# PanelDriver.net
KiCad netlist of a schematic drawn in Altium Designer
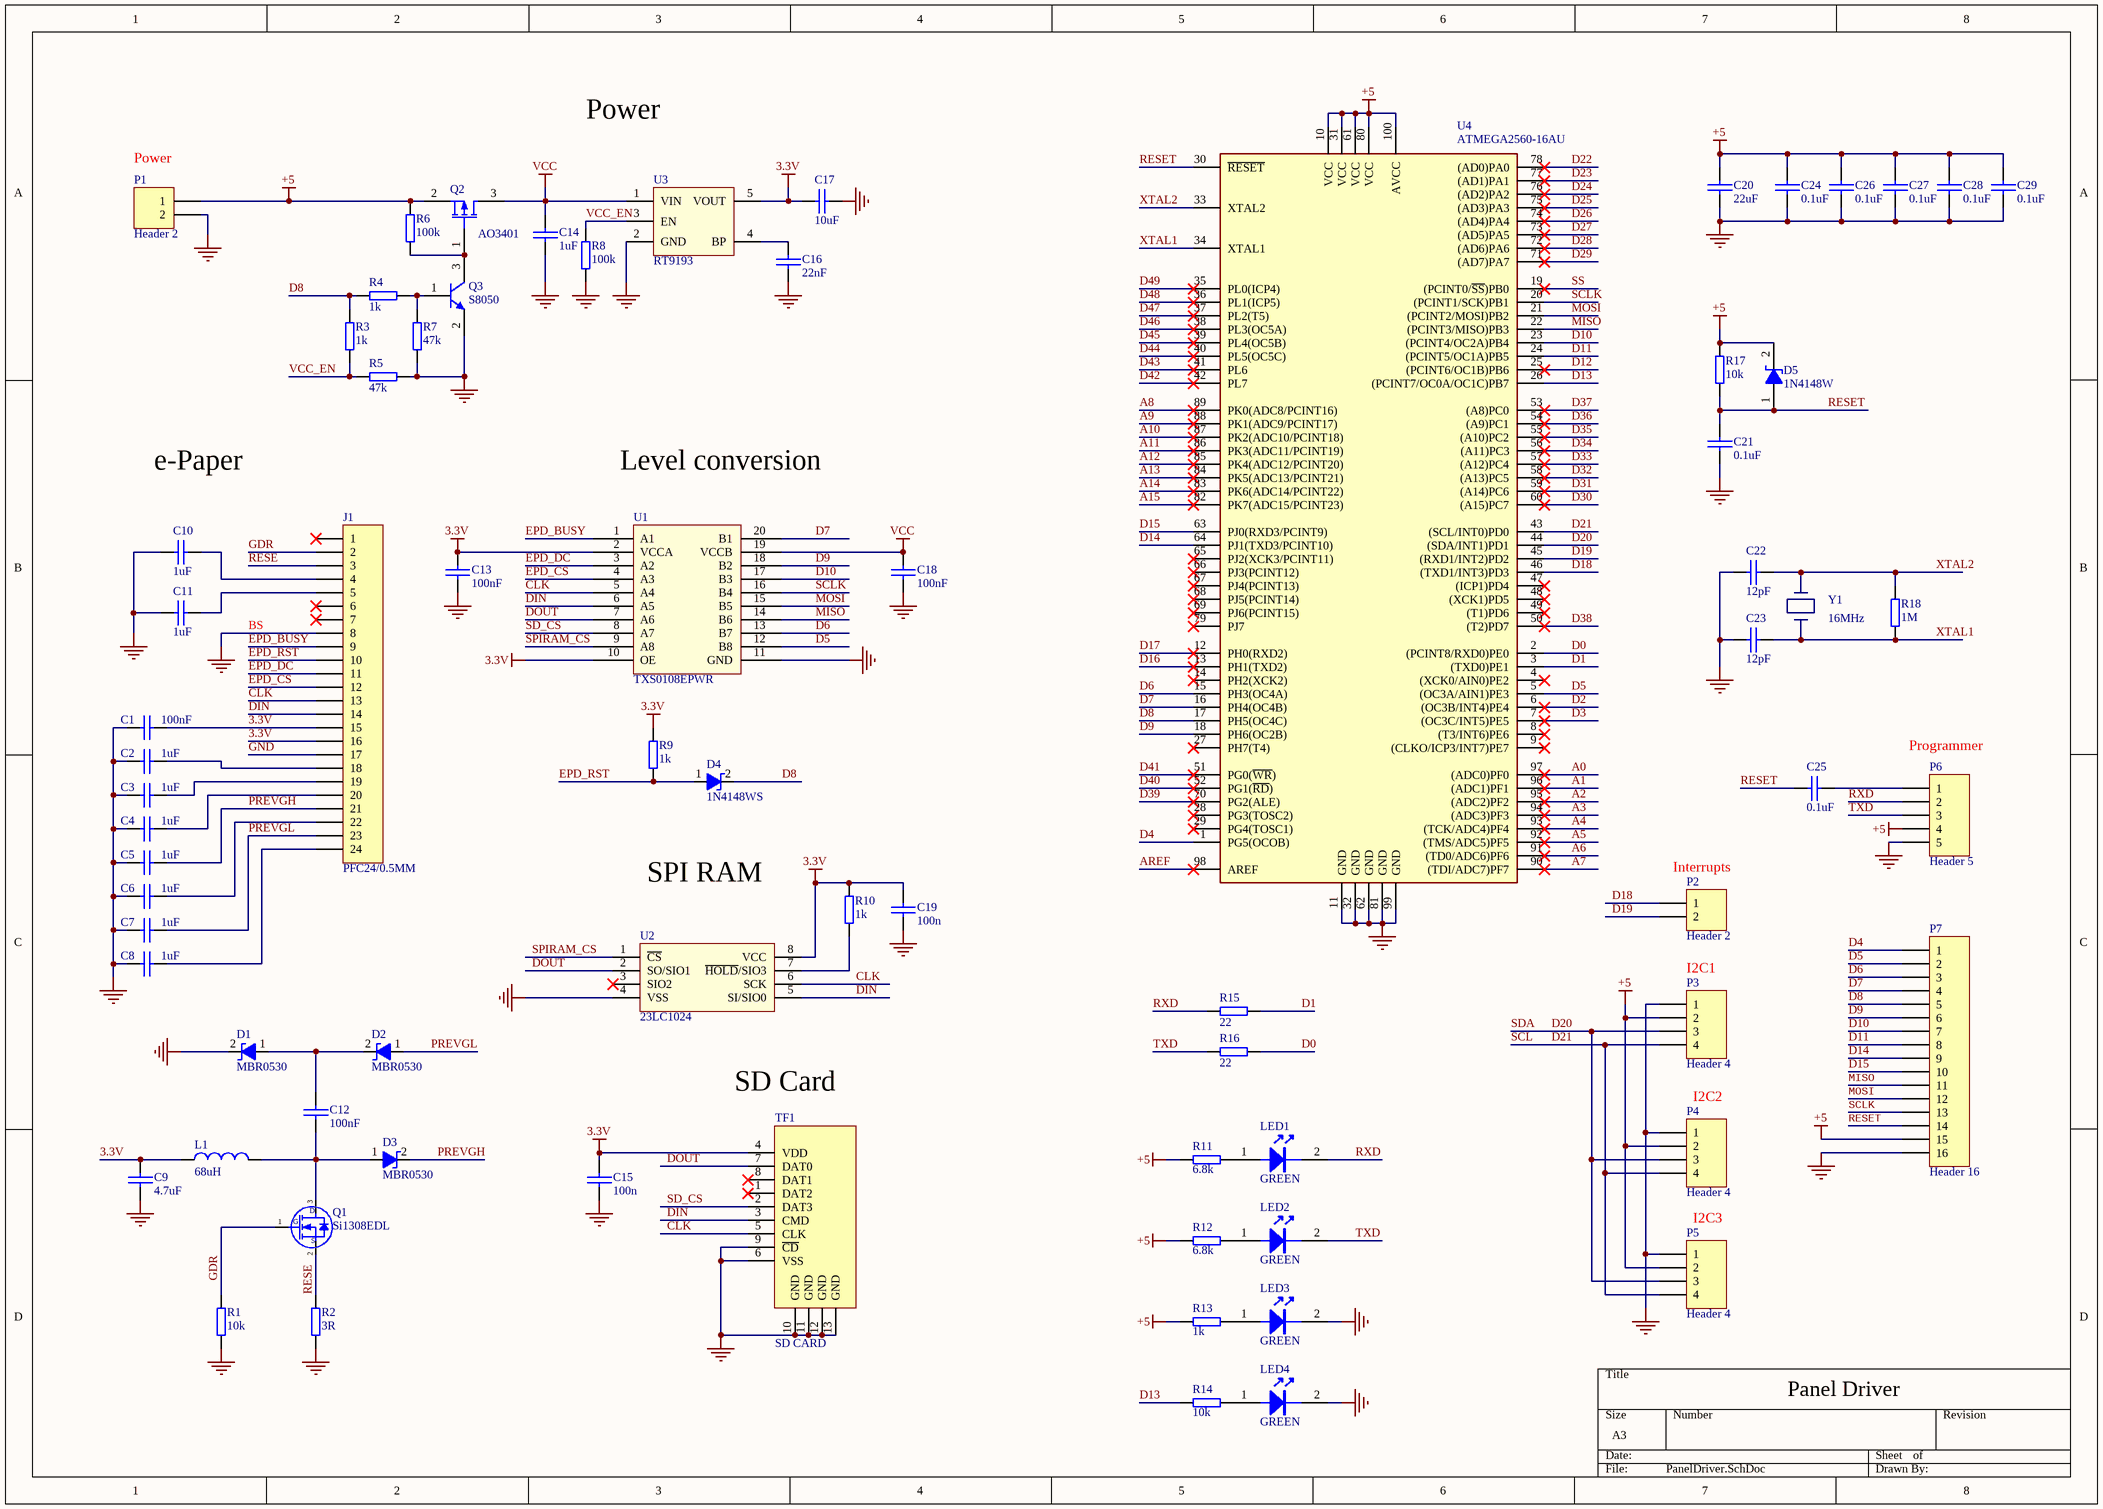
[diagram p0: PanelDriver.SchDoc]

(export (version "E")
  (design (tool "Eeschema 10.0.6"))
  (components
    (comp (ref "C1")
      (value "100nF")
      (footprint "C0603")
      (description "Capacitor")
      (fields (field (name "MANUFACTURER") "Any"))
      (libsource (lib "*") (part "C"))
    )
    (comp (ref "C2")
      (value "1uF")
      (footprint "C0603")
      (description "Capacitor")
      (fields (field (name "MANUFACTURER") "Any"))
      (libsource (lib "*") (part "C"))
    )
    (comp (ref "C3")
      (value "1uF")
      (footprint "C0603")
      (description "Capacitor")
      (fields (field (name "MANUFACTURER") "Any"))
      (libsource (lib "*") (part "C"))
    )
    (comp (ref "C4")
      (value "1uF")
      (footprint "C0603")
      (description "Capacitor")
      (fields (field (name "MANUFACTURER") "Any"))
      (libsource (lib "*") (part "C"))
    )
    (comp (ref "C5")
      (value "1uF")
      (footprint "C0603")
      (description "Capacitor")
      (fields (field (name "MANUFACTURER") "Any"))
      (libsource (lib "*") (part "C"))
    )
    (comp (ref "C6")
      (value "1uF")
      (footprint "C0603")
      (description "Capacitor")
      (fields (field (name "MANUFACTURER") "Any"))
      (libsource (lib "*") (part "C"))
    )
    (comp (ref "C7")
      (value "1uF")
      (footprint "C0603")
      (description "Capacitor")
      (fields (field (name "MANUFACTURER") "Any"))
      (libsource (lib "*") (part "C"))
    )
    (comp (ref "C8")
      (value "1uF")
      (footprint "C0603")
      (description "Capacitor")
      (fields (field (name "MANUFACTURER") "Any"))
      (libsource (lib "*") (part "C"))
    )
    (comp (ref "C9")
      (value "4.7uF")
      (footprint "C0603")
      (description "Capacitor")
      (fields (field (name "MANUFACTURER") "Any"))
      (libsource (lib "*") (part "C"))
    )
    (comp (ref "C10")
      (value "1uF")
      (footprint "C0603")
      (description "Capacitor")
      (fields (field (name "MANUFACTURER") "Any"))
      (libsource (lib "*") (part "C"))
    )
    (comp (ref "C11")
      (value "1uF")
      (footprint "C0603")
      (description "Capacitor")
      (fields (field (name "MANUFACTURER") "Any"))
      (libsource (lib "*") (part "C"))
    )
    (comp (ref "C12")
      (value "100nF")
      (footprint "C0603")
      (description "Capacitor")
      (fields (field (name "MANUFACTURER") "Any"))
      (libsource (lib "*") (part "C"))
    )
    (comp (ref "C13")
      (value "100nF")
      (footprint "C0603")
      (description "Capacitor")
      (fields (field (name "MANUFACTURER") "Any"))
      (libsource (lib "*") (part "C"))
    )
    (comp (ref "C14")
      (value "1uF")
      (footprint "C0603")
      (description "Capacitor")
      (fields (field (name "MANUFACTURER") "Any"))
      (libsource (lib "*") (part "C"))
    )
    (comp (ref "C15")
      (value "100n")
      (footprint "C0603")
      (description "Capacitor")
      (fields (field (name "MANUFACTURER") "Any"))
      (libsource (lib "*") (part "C"))
    )
    (comp (ref "C16")
      (value "22nF")
      (footprint "C0603")
      (description "Capacitor")
      (fields (field (name "VOLTAGE") "6.3V") (field (name "MANUFACTURER") "Any"))
      (libsource (lib "OE Modbus EMU") (part "C_100uF_6.3V_1206"))
    )
    (comp (ref "C17")
      (value "10uF")
      (footprint "C0603")
      (description "Capacitor")
      (fields (field (name "VOLTAGE") "6.3V") (field (name "MANUFACTURER") "Any"))
      (libsource (lib "OE Modbus EMU") (part "C_100uF_6.3V_1206"))
    )
    (comp (ref "C18")
      (value "100nF")
      (footprint "C0603")
      (description "Capacitor")
      (fields (field (name "MANUFACTURER") "Any"))
      (libsource (lib "*") (part "C"))
    )
    (comp (ref "C19")
      (value "100n")
      (footprint "C0603")
      (description "Capacitor")
      (fields (field (name "MANUFACTURER") "Any"))
      (libsource (lib "*") (part "C"))
    )
    (comp (ref "C20")
      (value "22uF")
      (footprint "C1206")
      (description "16V 22uF X7R ±10% 1206  Multilayer Ceramic Capacitors MLCC - SMD/SMT ROHS")
      (fields (field (name "MANUFACTURER") "Any"))
      (libsource (lib "*") (part "C"))
    )
    (comp (ref "C21")
      (value "0.1uF")
      (footprint "C0603")
      (description "25V 100nF X7R ±10% 0603  Multilayer Ceramic Capacitors MLCC - SMD/SMT ROHS")
      (fields (field (name "MANUFACTURER") "Any"))
      (libsource (lib "*") (part "C"))
    )
    (comp (ref "C22")
      (value "12pF")
      (footprint "C0603")
      (description "50V 22pF X7R ±10% 0603  Multilayer Ceramic Capacitors MLCC - SMD/SMT ROHS")
      (fields (field (name "VOLTAGE") "6.3V") (field (name "MANUFACTURER") "Any"))
      (libsource (lib "OE Modbus EMU") (part "C_100uF_6.3V_1206"))
    )
    (comp (ref "C23")
      (value "12pF")
      (footprint "C0603")
      (description "50V 22pF X7R ±10% 0603  Multilayer Ceramic Capacitors MLCC - SMD/SMT ROHS")
      (fields (field (name "VOLTAGE") "6.3V") (field (name "MANUFACTURER") "Any"))
      (libsource (lib "OE Modbus EMU") (part "C_100uF_6.3V_1206"))
    )
    (comp (ref "C24")
      (value "0.1uF")
      (footprint "C0603")
      (description "25V 100nF X7R ±10% 0603  Multilayer Ceramic Capacitors MLCC - SMD/SMT ROHS")
      (fields (field (name "MANUFACTURER") "Any"))
      (libsource (lib "*") (part "C"))
    )
    (comp (ref "C25")
      (value "0.1uF")
      (footprint "C0603")
      (description "25V 100nF X7R ±10% 0603  Multilayer Ceramic Capacitors MLCC - SMD/SMT ROHS")
      (fields (field (name "MANUFACTURER") "Any"))
      (libsource (lib "*") (part "C"))
    )
    (comp (ref "C26")
      (value "0.1uF")
      (footprint "C0603")
      (description "25V 100nF X7R ±10% 0603  Multilayer Ceramic Capacitors MLCC - SMD/SMT ROHS")
      (fields (field (name "MANUFACTURER") "Any"))
      (libsource (lib "*") (part "C"))
    )
    (comp (ref "C27")
      (value "0.1uF")
      (footprint "C0603")
      (description "25V 100nF X7R ±10% 0603  Multilayer Ceramic Capacitors MLCC - SMD/SMT ROHS")
      (fields (field (name "MANUFACTURER") "Any"))
      (libsource (lib "*") (part "C"))
    )
    (comp (ref "C28")
      (value "0.1uF")
      (footprint "C0603")
      (description "25V 100nF X7R ±10% 0603  Multilayer Ceramic Capacitors MLCC - SMD/SMT ROHS")
      (fields (field (name "MANUFACTURER") "Any") (field (name "JLCPCB PART NUMBER") "C307361"))
      (libsource (lib "") (part "C_1"))
    )
    (comp (ref "C29")
      (value "0.1uF")
      (footprint "C0603")
      (description "25V 100nF X7R ±10% 0603  Multilayer Ceramic Capacitors MLCC - SMD/SMT ROHS")
      (fields (field (name "MANUFACTURER") "Any"))
      (libsource (lib "*") (part "C"))
    )
    (comp (ref "D1")
      (value "MBR0530")
      (footprint "SOD123")
      (fields (field (name "MANUFACTURER") "Any"))
      (libsource (lib "OE Modbus EMU") (part "SS14F"))
    )
    (comp (ref "D2")
      (value "MBR0530")
      (footprint "SOD123")
      (fields (field (name "MANUFACTURER") "Any"))
      (libsource (lib "OE Modbus EMU") (part "SS14F"))
    )
    (comp (ref "D3")
      (value "MBR0530")
      (footprint "SOD123")
      (fields (field (name "MANUFACTURER") "Any"))
      (libsource (lib "OE Modbus EMU") (part "SS14F"))
    )
    (comp (ref "D4")
      (value "1N4148WS")
      (footprint "SOD-323")
      (fields (field (name "MANUFACTURER") "Any"))
      (libsource (lib "OE Modbus EMU") (part "SS14F"))
    )
    (comp (ref "D5")
      (value "1N4148W")
      (footprint "SOD123")
      (description "1N4148W-E3-08, Rectifier Diode Small Signal Switching Si 100V 0.15A 4ns 2-Pin SOD-123 T/R")
      (fields (field (name "MANUFACTURER") "Any"))
      (libsource (lib "A2560") (part "SS14F"))
    )
    (comp (ref "J1")
      (value "PFC24/0.5MM")
      (footprint "PFC24/0.5MM")
      (description "24 Position FFC, FPC Connector Contacts, Bottom 0.020\" (0.50mm) Surface Mount, Right Angle")
      (fields
        (field (name "MANUFACTURER") "MOLEX")
        (field (name "MANUFACTURER PART NUMBER") "0524372471")
        (field (name "PUBLISHER") "Altium Limited")
      )
      (libsource (lib "PanelDriver") (part "PFC24/0.5MMHeader 24"))
    )
    (comp (ref "L1")
      (value "68uH")
      (footprint "CD43")
      (description "SMD, 4x4mm  Inductor")
      (fields (field (name "MANUFACTURER") "Any"))
      (libsource (lib "OE Modbus EMU") (part "IND"))
    )
    (comp (ref "LED1")
      (value "GREEN")
      (footprint "LED-0603-GREEN")
      (description "0603  Light Emitting Diodes (LED) ROHS")
      (fields (field (name "MANUFACTURER") "Any") (field (name "JLCPCB PART NUMBER") "C965812"))
      (libsource (lib "A2560") (part "LED"))
    )
    (comp (ref "LED2")
      (value "GREEN")
      (footprint "LED-0603-GREEN")
      (description "0603  Light Emitting Diodes (LED) ROHS")
      (fields (field (name "MANUFACTURER") "Any") (field (name "JLCPCB PART NUMBER") "C965812"))
      (libsource (lib "A2560") (part "LED"))
    )
    (comp (ref "LED3")
      (value "GREEN")
      (footprint "LED-0603-GREEN")
      (description "0603  Light Emitting Diodes (LED) ROHS")
      (fields (field (name "MANUFACTURER") "Any") (field (name "JLCPCB PART NUMBER") "C965812"))
      (libsource (lib "A2560") (part "LED"))
    )
    (comp (ref "LED4")
      (value "GREEN")
      (footprint "LED-0603-GREEN")
      (description "0603  Light Emitting Diodes (LED) ROHS")
      (fields (field (name "MANUFACTURER") "Any") (field (name "JLCPCB PART NUMBER") "C965812"))
      (libsource (lib "A2560") (part "LED"))
    )
    (comp (ref "P1")
      (value "Header 2")
      (footprint "HDR1X2")
      (description "Header, 2-Pin")
      (fields (field (name "PUBLISHER") "Altium Limited"))
      (libsource (lib "") (part "Header 2_1"))
    )
    (comp (ref "P2")
      (value "Header 2")
      (footprint "HDR1X2")
      (description "Header, 2-Pin")
      (fields (field (name "PUBLISHER") "Altium Limited"))
      (libsource (lib "Miscellaneous Connectors") (part "Header 2"))
    )
    (comp (ref "P3")
      (value "Header 4")
      (footprint "HDR1X4")
      (description "Header, 4-Pin")
      (fields (field (name "PUBLISHER") "Altium Limited"))
      (libsource (lib "Miscellaneous Connectors") (part "Header 4"))
    )
    (comp (ref "P4")
      (value "Header 4")
      (footprint "HDR1X4")
      (description "Header, 4-Pin")
      (fields (field (name "PUBLISHER") "Altium Limited"))
      (libsource (lib "Miscellaneous Connectors") (part "Header 4"))
    )
    (comp (ref "P5")
      (value "Header 4")
      (footprint "HDR1X4")
      (description "Header, 4-Pin")
      (fields (field (name "PUBLISHER") "Altium Limited"))
      (libsource (lib "Miscellaneous Connectors") (part "Header 4"))
    )
    (comp (ref "P6")
      (value "Header 5")
      (footprint "HDR1X5")
      (description "Header, 5-Pin")
      (fields (field (name "MANUFACTURER") "Any") (field (name "PUBLISHER") "Altium Limited"))
      (libsource (lib "Miscellaneous Connectors") (part "Header 5"))
    )
    (comp (ref "P7")
      (value "Header 16")
      (footprint "HDR1X16")
      (description "Header, 16-Pin")
      (fields (field (name "PUBLISHER") "Altium Limited"))
      (libsource (lib "Miscellaneous Connectors") (part "Header 16"))
    )
    (comp (ref "Q1")
      (value "Si1308EDL")
      (footprint "SOT323-3")
      (fields (field (name "MANUFACTURER") "Any"))
      (libsource (lib "PanelDriver") (part "Si1308EDL"))
    )
    (comp (ref "Q2")
      (value "AO3401")
      (footprint "SOT-23")
      (fields (field (name "MANUFACTURER") "Any"))
      (libsource (lib "All Libs") (part "ZXMP6A13FTA"))
    )
    (comp (ref "Q3")
      (value "S8050")
      (footprint "SOT-23")
      (fields (field (name "MANUFACTURER") "Any"))
      (libsource (lib "All Libs") (part "NPN_BJT"))
    )
    (comp (ref "R1")
      (value "10k")
      (footprint "R0603")
      (description "Resistor")
      (fields (field (name "MANUFACTURER") "Any"))
      (libsource (lib "PanelDriver") (part "R"))
    )
    (comp (ref "R2")
      (value "3R")
      (footprint "R0603")
      (description "Resistor")
      (fields (field (name "MANUFACTURER") "Any"))
      (libsource (lib "PanelDriver") (part "R"))
    )
    (comp (ref "R3")
      (value "1k")
      (footprint "R0603")
      (description "Resistor")
      (fields (field (name "MANUFACTURER") "Any"))
      (libsource (lib "PanelDriver") (part "R"))
    )
    (comp (ref "R4")
      (value "1k")
      (footprint "R0603")
      (description "Resistor")
      (fields (field (name "MANUFACTURER") "Any"))
      (libsource (lib "PanelDriver") (part "R"))
    )
    (comp (ref "R5")
      (value "47k")
      (footprint "R0603")
      (description "Resistor")
      (fields (field (name "MANUFACTURER") "Any"))
      (libsource (lib "PanelDriver") (part "R"))
    )
    (comp (ref "R6")
      (value "100k")
      (footprint "R0603")
      (description "Resistor")
      (fields (field (name "MANUFACTURER") "Any"))
      (libsource (lib "PanelDriver") (part "R"))
    )
    (comp (ref "R7")
      (value "47k")
      (footprint "R0603")
      (description "Resistor")
      (fields (field (name "MANUFACTURER") "Any"))
      (libsource (lib "PanelDriver") (part "R"))
    )
    (comp (ref "R8")
      (value "100k")
      (footprint "R0603")
      (description "Resistor")
      (fields (field (name "MANUFACTURER") "Any"))
      (libsource (lib "PanelDriver") (part "R"))
    )
    (comp (ref "R9")
      (value "1k")
      (footprint "R0603")
      (description "Resistor")
      (fields (field (name "MANUFACTURER") "Any"))
      (libsource (lib "PanelDriver") (part "R"))
    )
    (comp (ref "R10")
      (value "1k")
      (footprint "R0603")
      (description "Resistor")
      (fields (field (name "MANUFACTURER") "Any"))
      (libsource (lib "PanelDriver") (part "R"))
    )
    (comp (ref "R11")
      (value "6.8k")
      (footprint "R0603")
      (description "125mW Thick Film Resistors ±100ppm/℃ ±5% 6.8kΩ 0603  Chip Resistor - Surface Mount ROHS")
      (fields (field (name "MANUFACTURER") "Any") (field (name "JLCPCB PART NUMBER") "C100046"))
      (libsource (lib "*") (part "R"))
    )
    (comp (ref "R12")
      (value "6.8k")
      (footprint "R0603")
      (description "125mW Thick Film Resistors ±100ppm/℃ ±5% 6.8kΩ 0603  Chip Resistor - Surface Mount ROHS")
      (fields (field (name "MANUFACTURER") "Any") (field (name "JLCPCB PART NUMBER") "C100046"))
      (libsource (lib "*") (part "R"))
    )
    (comp (ref "R13")
      (value "1k")
      (footprint "R0603")
      (description "125mW Thick Film Resistors ±100ppm/℃ ±5% 1kΩ 0603  Chip Resistor - Surface Mount ROHS")
      (fields (field (name "MANUFACTURER") "Any") (field (name "JLCPCB PART NUMBER") "C100046"))
      (libsource (lib "*") (part "R"))
    )
    (comp (ref "R14")
      (value "10k")
      (footprint "R0603")
      (description "125mW Thick Film Resistors ±100ppm/℃ ±5% 10kΩ 0603  Chip Resistor - Surface Mount ROHS")
      (fields (field (name "MANUFACTURER") "Any") (field (name "JLCPCB PART NUMBER") "C100046"))
      (libsource (lib "*") (part "R"))
    )
    (comp (ref "R15")
      (value "22")
      (footprint "R0603")
      (description "125mW Thick Film Resistors ±100ppm/℃ ±5% 22Ω 0603  Chip Resistor - Surface Mount ROHS")
      (fields (field (name "MANUFACTURER") "Any"))
      (libsource (lib "PanelDriver") (part "R"))
    )
    (comp (ref "R16")
      (value "22")
      (footprint "R0603")
      (description "125mW Thick Film Resistors ±100ppm/℃ ±5% 22Ω 0603  Chip Resistor - Surface Mount ROHS")
      (fields (field (name "MANUFACTURER") "Any"))
      (libsource (lib "PanelDriver") (part "R"))
    )
    (comp (ref "R17")
      (value "10k")
      (footprint "R0603")
      (description "125mW Thick Film Resistors ±100ppm/℃ ±5% 10kΩ 0603  Chip Resistor - Surface Mount ROHS")
      (fields (field (name "MANUFACTURER") "Any"))
      (libsource (lib "PanelDriver") (part "R"))
    )
    (comp (ref "R18")
      (value "1M")
      (footprint "R0603")
      (description "125mW Thick Film Resistors ±100ppm/℃ ±5% 1M 0603  Chip Resistor - Surface Mount ROHS")
      (fields (field (name "MANUFACTURER") "Any"))
      (libsource (lib "PanelDriver") (part "R"))
    )
    (comp (ref "TF1")
      (value "SD CARD")
      (footprint "L-KLS1-TF-003-uSD")
      (description "SDCARD")
      (fields
        (field (name "PARTNUMBER") "693071010811")
        (field (name "MANUFACTURER") "KLS electronic co ltd")
      )
      (libsource (lib "PanelDriver") (part "SD CARD"))
    )
    (comp (ref "U1")
      (value "TXS0108EPWR")
      (footprint "TSSOP-20_0.65mm")
      (fields (field (name "MANUFACTURER") "Any"))
      (libsource (lib "PanelDriver") (part "TXS0108EPWR"))
    )
    (comp (ref "U2")
      (value "23LC1024")
      (footprint "SO8")
      (fields (field (name "MANUFACTURER") "Any"))
      (libsource (lib "PanelDriver") (part "23LC1024"))
    )
    (comp (ref "U3")
      (value "RT9193")
      (footprint "SOT23-5")
      (fields (field (name "MANUFACTURER") "Any"))
      (libsource (lib "PanelDriver") (part "RT9193"))
    )
    (comp (ref "U4")
      (value "ATMEGA2560-16AU")
      (footprint "TQFP100A")
      (fields (field (name "MANUFACTURER") "Microchip Tech"))
      (libsource (lib "A2560") (part "ATMEGA2560-16AU"))
    )
    (comp (ref "Y1")
      (value "16MHz")
      (footprint "HC-49/US-SMD")
      (description "Crystal 16MHz 12pF SMD")
      (fields (field (name "MANUFACTURER") "Any"))
      (libsource (lib "A2560") (part "Crystal-16MHz"))
    )
  )
  (nets
    (net (code "1") (name "+5") (class "Default")
      (node (ref "C20") (pin "2") (pintype "passive"))
      (node (ref "C24") (pin "2") (pintype "passive"))
      (node (ref "C26") (pin "2") (pintype "passive"))
      (node (ref "C27") (pin "2") (pintype "passive"))
      (node (ref "C28") (pin "2") (pintype "passive"))
      (node (ref "C29") (pin "1") (pintype "passive"))
      (node (ref "D5") (pin "2") (pinfunction "K_2") (pintype "passive"))
      (node (ref "P1") (pin "1") (pinfunction "1_1") (pintype "passive"))
      (node (ref "P3") (pin "2") (pinfunction "2_2") (pintype "passive"))
      (node (ref "P4") (pin "2") (pinfunction "2_2") (pintype "passive"))
      (node (ref "P5") (pin "2") (pinfunction "2_2") (pintype "passive"))
      (node (ref "P6") (pin "4") (pinfunction "4_4") (pintype "passive"))
      (node (ref "P7") (pin "15") (pinfunction "15_15") (pintype "passive"))
      (node (ref "Q2") (pin "2") (pinfunction "S_2") (pintype "passive"))
      (node (ref "R11") (pin "1") (pinfunction "1_1") (pintype "passive"))
      (node (ref "R12") (pin "1") (pinfunction "1_1") (pintype "passive"))
      (node (ref "R13") (pin "1") (pinfunction "1_1") (pintype "passive"))
      (node (ref "R17") (pin "2") (pinfunction "2_2") (pintype "passive"))
      (node (ref "R6") (pin "1") (pinfunction "1_1") (pintype "passive"))
      (node (ref "U4") (pin "10") (pinfunction "VCC_10") (pintype "passive"))
      (node (ref "U4") (pin "100") (pinfunction "AVCC_100") (pintype "passive"))
      (node (ref "U4") (pin "31") (pinfunction "VCC_31") (pintype "passive"))
      (node (ref "U4") (pin "61") (pinfunction "VCC_61") (pintype "passive"))
      (node (ref "U4") (pin "80") (pinfunction "VCC_80") (pintype "passive"))
    )
    (net (code "2") (name "/A0") (class "Default")
      (node (ref "U4") (pin "97") (pinfunction "(ADC0)PF0_97") (pintype "passive+no_connect"))
    )
    (net (code "3") (name "/A1") (class "Default")
      (node (ref "U4") (pin "96") (pinfunction "(ADC1)PF1_96") (pintype "passive+no_connect"))
    )
    (net (code "4") (name "/A2") (class "Default")
      (node (ref "U4") (pin "95") (pinfunction "(ADC2)PF2_95") (pintype "passive+no_connect"))
    )
    (net (code "5") (name "/A3") (class "Default")
      (node (ref "U4") (pin "94") (pinfunction "(ADC3)PF3_94") (pintype "passive+no_connect"))
    )
    (net (code "6") (name "/A4") (class "Default")
      (node (ref "U4") (pin "93") (pinfunction "(TCK/ADC4)PF4_93") (pintype "passive+no_connect"))
    )
    (net (code "7") (name "/A5") (class "Default")
      (node (ref "U4") (pin "92") (pinfunction "(TMS/ADC5)PF5_92") (pintype "passive+no_connect"))
    )
    (net (code "8") (name "/A6") (class "Default")
      (node (ref "U4") (pin "91") (pinfunction "(TD0/ADC6)PF6_91") (pintype "passive+no_connect"))
    )
    (net (code "9") (name "/A7") (class "Default")
      (node (ref "U4") (pin "90") (pinfunction "(TDI/ADC7)PF7_90") (pintype "passive+no_connect"))
    )
    (net (code "10") (name "/A8") (class "Default")
      (node (ref "U4") (pin "89") (pinfunction "PK0(ADC8/PCINT16)_89") (pintype "passive+no_connect"))
    )
    (net (code "11") (name "/A9") (class "Default")
      (node (ref "U4") (pin "88") (pinfunction "PK1(ADC9/PCINT17)_88") (pintype "passive+no_connect"))
    )
    (net (code "12") (name "/A10") (class "Default")
      (node (ref "U4") (pin "87") (pinfunction "PK2(ADC10/PCINT18)_87") (pintype "passive+no_connect"))
    )
    (net (code "13") (name "/A11") (class "Default")
      (node (ref "U4") (pin "86") (pinfunction "PK3(ADC11/PCINT19)_86") (pintype "passive+no_connect"))
    )
    (net (code "14") (name "/A12") (class "Default")
      (node (ref "U4") (pin "85") (pinfunction "PK4(ADC12/PCINT20)_85") (pintype "passive+no_connect"))
    )
    (net (code "15") (name "/A13") (class "Default")
      (node (ref "U4") (pin "84") (pinfunction "PK5(ADC13/PCINT21)_84") (pintype "passive+no_connect"))
    )
    (net (code "16") (name "/A14") (class "Default")
      (node (ref "U4") (pin "83") (pinfunction "PK6(ADC14/PCINT22)_83") (pintype "passive+no_connect"))
    )
    (net (code "17") (name "/A15") (class "Default")
      (node (ref "U4") (pin "82") (pinfunction "PK7(ADC15/PCINT23)_82") (pintype "passive+no_connect"))
    )
    (net (code "18") (name "/AREF") (class "Default")
      (node (ref "U4") (pin "98") (pinfunction "AREF_98") (pintype "passive+no_connect"))
    )
    (net (code "19") (name "/CLK") (class "Default")
      (node (ref "J1") (pin "13") (pinfunction "13_13") (pintype "passive"))
      (node (ref "TF1") (pin "5") (pinfunction "CLK_5") (pintype "passive"))
      (node (ref "U1") (pin "5") (pinfunction "A4_5") (pintype "passive"))
      (node (ref "U2") (pin "6") (pinfunction "SCK_6") (pintype "passive"))
    )
    (net (code "20") (name "/D0") (class "Default")
      (node (ref "R16") (pin "1") (pinfunction "1_1") (pintype "passive"))
      (node (ref "U4") (pin "2") (pinfunction "(PCINT8/RXD0)PE0_2") (pintype "passive"))
    )
    (net (code "21") (name "/D1") (class "Default")
      (node (ref "R15") (pin "1") (pinfunction "1_1") (pintype "passive"))
      (node (ref "U4") (pin "3") (pinfunction "(TXD0)PE1_3") (pintype "passive"))
    )
    (net (code "22") (name "/D2") (class "Default")
      (node (ref "U4") (pin "6") (pinfunction "(OC3B/INT4)PE4_6") (pintype "passive+no_connect"))
    )
    (net (code "23") (name "/D3") (class "Default")
      (node (ref "U4") (pin "7") (pinfunction "(OC3C/INT5)PE5_7") (pintype "passive+no_connect"))
    )
    (net (code "24") (name "/D4") (class "Default")
      (node (ref "P7") (pin "1") (pinfunction "1_1") (pintype "passive"))
      (node (ref "U4") (pin "1") (pinfunction "PG5(OCOB)_1") (pintype "passive"))
    )
    (net (code "25") (name "/D5") (class "Default")
      (node (ref "P7") (pin "2") (pinfunction "2_2") (pintype "passive"))
      (node (ref "U1") (pin "12") (pinfunction "B8_12") (pintype "passive"))
      (node (ref "U4") (pin "5") (pinfunction "(OC3A/AIN1)PE3_5") (pintype "passive"))
    )
    (net (code "26") (name "/D6") (class "Default")
      (node (ref "P7") (pin "3") (pinfunction "3_3") (pintype "passive"))
      (node (ref "U1") (pin "13") (pinfunction "B7_13") (pintype "passive"))
      (node (ref "U4") (pin "15") (pinfunction "PH3(OC4A)_15") (pintype "passive"))
    )
    (net (code "27") (name "/D7") (class "Default")
      (node (ref "P7") (pin "4") (pinfunction "4_4") (pintype "passive"))
      (node (ref "U1") (pin "20") (pinfunction "B1_20") (pintype "passive"))
      (node (ref "U4") (pin "16") (pinfunction "PH4(OC4B)_16") (pintype "passive"))
    )
    (net (code "28") (name "/D8") (class "Default")
      (node (ref "D4") (pin "2") (pinfunction "K_2") (pintype "passive"))
      (node (ref "P7") (pin "5") (pinfunction "5_5") (pintype "passive"))
      (node (ref "R3") (pin "2") (pinfunction "2_2") (pintype "passive"))
      (node (ref "R4") (pin "1") (pinfunction "1_1") (pintype "passive"))
      (node (ref "U4") (pin "17") (pinfunction "PH5(OC4C)_17") (pintype "passive"))
    )
    (net (code "29") (name "/D9") (class "Default")
      (node (ref "P7") (pin "6") (pinfunction "6_6") (pintype "passive"))
      (node (ref "U1") (pin "18") (pinfunction "B2_18") (pintype "passive"))
      (node (ref "U4") (pin "18") (pinfunction "PH6(OC2B)_18") (pintype "passive"))
    )
    (net (code "30") (name "/D10") (class "Default")
      (node (ref "P7") (pin "7") (pinfunction "7_7") (pintype "passive"))
      (node (ref "U1") (pin "17") (pinfunction "B3_17") (pintype "passive"))
      (node (ref "U4") (pin "23") (pinfunction "(PCINT4/OC2A)PB4_23") (pintype "passive"))
    )
    (net (code "31") (name "/D11") (class "Default")
      (node (ref "P7") (pin "8") (pinfunction "8_8") (pintype "passive"))
      (node (ref "U4") (pin "24") (pinfunction "(PCINT5/OC1A)PB5_24") (pintype "passive"))
    )
    (net (code "32") (name "/D12") (class "Default")
      (node (ref "U4") (pin "25") (pinfunction "(PCINT6/OC1B)PB6_25") (pintype "passive+no_connect"))
    )
    (net (code "33") (name "/D13") (class "Default")
      (node (ref "R14") (pin "1") (pinfunction "1_1") (pintype "passive"))
      (node (ref "U4") (pin "26") (pinfunction "(PCINT7/OC0A/OC1C)PB7_26") (pintype "passive"))
    )
    (net (code "34") (name "/D14") (class "Default")
      (node (ref "P7") (pin "9") (pinfunction "9_9") (pintype "passive"))
      (node (ref "U4") (pin "64") (pinfunction "PJ1(TXD3/PCINT10)_64") (pintype "passive"))
    )
    (net (code "35") (name "/D15") (class "Default")
      (node (ref "P7") (pin "10") (pinfunction "10_10") (pintype "passive"))
      (node (ref "U4") (pin "63") (pinfunction "PJ0(RXD3/PCINT9)_63") (pintype "passive"))
    )
    (net (code "36") (name "/D16") (class "Default")
      (node (ref "U4") (pin "13") (pinfunction "PH1(TXD2)_13") (pintype "passive+no_connect"))
    )
    (net (code "37") (name "/D17") (class "Default")
      (node (ref "U4") (pin "12") (pinfunction "PH0(RXD2)_12") (pintype "passive+no_connect"))
    )
    (net (code "38") (name "/D18") (class "Default")
      (node (ref "P2") (pin "1") (pinfunction "1_1") (pintype "passive"))
      (node (ref "U4") (pin "46") (pinfunction "(TXD1/INT3)PD3_46") (pintype "passive"))
    )
    (net (code "39") (name "/D19") (class "Default")
      (node (ref "P2") (pin "2") (pinfunction "2_2") (pintype "passive"))
      (node (ref "U4") (pin "45") (pinfunction "(RXD1/INT2)PD2_45") (pintype "passive"))
    )
    (net (code "40") (name "/D20") (class "Default")
      (node (ref "P3") (pin "3") (pinfunction "3_3") (pintype "passive"))
      (node (ref "P4") (pin "3") (pinfunction "3_3") (pintype "passive"))
      (node (ref "P5") (pin "3") (pinfunction "3_3") (pintype "passive"))
      (node (ref "U4") (pin "44") (pinfunction "(SDA/INT1)PD1_44") (pintype "passive"))
    )
    (net (code "41") (name "/D21") (class "Default")
      (node (ref "P3") (pin "4") (pinfunction "4_4") (pintype "passive"))
      (node (ref "P4") (pin "4") (pinfunction "4_4") (pintype "passive"))
      (node (ref "P5") (pin "4") (pinfunction "4_4") (pintype "passive"))
      (node (ref "U4") (pin "43") (pinfunction "(SCL/INT0)PD0_43") (pintype "passive"))
    )
    (net (code "42") (name "/D22") (class "Default")
      (node (ref "U4") (pin "78") (pinfunction "(AD0)PA0_78") (pintype "passive+no_connect"))
    )
    (net (code "43") (name "/D23") (class "Default")
      (node (ref "U4") (pin "77") (pinfunction "(AD1)PA1_77") (pintype "passive+no_connect"))
    )
    (net (code "44") (name "/D24") (class "Default")
      (node (ref "U4") (pin "76") (pinfunction "(AD2)PA2_76") (pintype "passive+no_connect"))
    )
    (net (code "45") (name "/D25") (class "Default")
      (node (ref "U4") (pin "75") (pinfunction "(AD3)PA3_75") (pintype "passive+no_connect"))
    )
    (net (code "46") (name "/D26") (class "Default")
      (node (ref "U4") (pin "74") (pinfunction "(AD4)PA4_74") (pintype "passive+no_connect"))
    )
    (net (code "47") (name "/D27") (class "Default")
      (node (ref "U4") (pin "73") (pinfunction "(AD5)PA5_73") (pintype "passive+no_connect"))
    )
    (net (code "48") (name "/D28") (class "Default")
      (node (ref "U4") (pin "72") (pinfunction "(AD6)PA6_72") (pintype "passive+no_connect"))
    )
    (net (code "49") (name "/D29") (class "Default")
      (node (ref "U4") (pin "71") (pinfunction "(AD7)PA7_71") (pintype "passive+no_connect"))
    )
    (net (code "50") (name "/D30") (class "Default")
      (node (ref "U4") (pin "60") (pinfunction "(A15)PC7_60") (pintype "passive+no_connect"))
    )
    (net (code "51") (name "/D31") (class "Default")
      (node (ref "U4") (pin "59") (pinfunction "(A14)PC6_59") (pintype "passive+no_connect"))
    )
    (net (code "52") (name "/D32") (class "Default")
      (node (ref "U4") (pin "58") (pinfunction "(A13)PC5_58") (pintype "passive+no_connect"))
    )
    (net (code "53") (name "/D33") (class "Default")
      (node (ref "U4") (pin "57") (pinfunction "(A12)PC4_57") (pintype "passive+no_connect"))
    )
    (net (code "54") (name "/D34") (class "Default")
      (node (ref "U4") (pin "56") (pinfunction "(A11)PC3_56") (pintype "passive+no_connect"))
    )
    (net (code "55") (name "/D35") (class "Default")
      (node (ref "U4") (pin "55") (pinfunction "(A10)PC2_55") (pintype "passive+no_connect"))
    )
    (net (code "56") (name "/D36") (class "Default")
      (node (ref "U4") (pin "54") (pinfunction "(A9)PC1_54") (pintype "passive+no_connect"))
    )
    (net (code "57") (name "/D37") (class "Default")
      (node (ref "U4") (pin "53") (pinfunction "(A8)PC0_53") (pintype "passive+no_connect"))
    )
    (net (code "58") (name "/D38") (class "Default")
      (node (ref "U4") (pin "50") (pinfunction "(T2)PD7_50") (pintype "passive+no_connect"))
    )
    (net (code "59") (name "/D39") (class "Default")
      (node (ref "U4") (pin "70") (pinfunction "PG2(ALE)_70") (pintype "passive+no_connect"))
    )
    (net (code "60") (name "/D40") (class "Default")
      (node (ref "U4") (pin "52") (pinfunction "PG1(~{RD})_52") (pintype "passive+no_connect"))
    )
    (net (code "61") (name "/D41") (class "Default")
      (node (ref "U4") (pin "51") (pinfunction "PG0(~{WR})_51") (pintype "passive+no_connect"))
    )
    (net (code "62") (name "/D42") (class "Default")
      (node (ref "U4") (pin "42") (pinfunction "PL7_42") (pintype "passive+no_connect"))
    )
    (net (code "63") (name "/D43") (class "Default")
      (node (ref "U4") (pin "41") (pinfunction "PL6_41") (pintype "passive+no_connect"))
    )
    (net (code "64") (name "/D44") (class "Default")
      (node (ref "U4") (pin "40") (pinfunction "PL5(OC5C)_40") (pintype "passive+no_connect"))
    )
    (net (code "65") (name "/D45") (class "Default")
      (node (ref "U4") (pin "39") (pinfunction "PL4(OC5B)_39") (pintype "passive+no_connect"))
    )
    (net (code "66") (name "/D46") (class "Default")
      (node (ref "U4") (pin "38") (pinfunction "PL3(OC5A)_38") (pintype "passive+no_connect"))
    )
    (net (code "67") (name "/D47") (class "Default")
      (node (ref "U4") (pin "37") (pinfunction "PL2(T5)_37") (pintype "passive+no_connect"))
    )
    (net (code "68") (name "/D48") (class "Default")
      (node (ref "U4") (pin "36") (pinfunction "PL1(ICP5)_36") (pintype "passive+no_connect"))
    )
    (net (code "69") (name "/D49") (class "Default")
      (node (ref "U4") (pin "35") (pinfunction "PL0(ICP4)_35") (pintype "passive+no_connect"))
    )
    (net (code "70") (name "/DIN") (class "Default")
      (node (ref "J1") (pin "14") (pinfunction "14_14") (pintype "passive"))
      (node (ref "TF1") (pin "3") (pinfunction "CMD_3") (pintype "passive"))
      (node (ref "U1") (pin "6") (pinfunction "A5_6") (pintype "passive"))
      (node (ref "U2") (pin "5") (pinfunction "SI/SIO0_5") (pintype "passive"))
    )
    (net (code "71") (name "/DOUT") (class "Default")
      (node (ref "TF1") (pin "7") (pinfunction "DAT0_7") (pintype "passive"))
      (node (ref "U1") (pin "7") (pinfunction "A6_7") (pintype "passive"))
      (node (ref "U2") (pin "2") (pinfunction "SO/SIO1_2") (pintype "passive"))
    )
    (net (code "72") (name "/EPD_BUSY") (class "Default")
      (node (ref "J1") (pin "9") (pinfunction "9_9") (pintype "passive"))
      (node (ref "U1") (pin "1") (pinfunction "A1_1") (pintype "passive"))
    )
    (net (code "73") (name "/EPD_CS") (class "Default")
      (node (ref "J1") (pin "12") (pinfunction "12_12") (pintype "passive"))
      (node (ref "U1") (pin "4") (pinfunction "A3_4") (pintype "passive"))
    )
    (net (code "74") (name "/EPD_DC") (class "Default")
      (node (ref "J1") (pin "11") (pinfunction "11_11") (pintype "passive"))
      (node (ref "U1") (pin "3") (pinfunction "A2_3") (pintype "passive"))
    )
    (net (code "75") (name "/EPD_RST") (class "Default")
      (node (ref "D4") (pin "1") (pinfunction "A_1") (pintype "passive"))
      (node (ref "J1") (pin "10") (pinfunction "10_10") (pintype "passive"))
      (node (ref "R9") (pin "1") (pinfunction "1_1") (pintype "passive"))
    )
    (net (code "76") (name "/GDR") (class "Default")
      (node (ref "J1") (pin "2") (pinfunction "2_2") (pintype "passive"))
      (node (ref "Q1") (pin "1") (pinfunction "G_1") (pintype "passive"))
      (node (ref "R1") (pin "1") (pinfunction "1_1") (pintype "passive"))
    )
    (net (code "77") (name "/MISO") (class "Default")
      (node (ref "P7") (pin "11") (pinfunction "11_11") (pintype "passive"))
      (node (ref "U1") (pin "14") (pinfunction "B6_14") (pintype "passive"))
      (node (ref "U4") (pin "22") (pinfunction "(PCINT3/MISO)PB3_22") (pintype "passive"))
    )
    (net (code "78") (name "/MOSI") (class "Default")
      (node (ref "P7") (pin "12") (pinfunction "12_12") (pintype "passive"))
      (node (ref "U1") (pin "15") (pinfunction "B5_15") (pintype "passive"))
      (node (ref "U4") (pin "21") (pinfunction "(PCINT2/MOSI)PB2_21") (pintype "passive"))
    )
    (net (code "79") (name "/PREVGH") (class "Default")
      (node (ref "C5") (pin "1") (pintype "passive"))
      (node (ref "D3") (pin "2") (pinfunction "K_2") (pintype "passive"))
      (node (ref "J1") (pin "21") (pinfunction "21_21") (pintype "passive"))
    )
    (net (code "80") (name "/PREVGL") (class "Default")
      (node (ref "C7") (pin "1") (pintype "passive"))
      (node (ref "D2") (pin "1") (pinfunction "A_1") (pintype "passive"))
      (node (ref "J1") (pin "23") (pinfunction "23_23") (pintype "passive"))
    )
    (net (code "81") (name "/RESE") (class "Default")
      (node (ref "J1") (pin "3") (pinfunction "3_3") (pintype "passive"))
      (node (ref "Q1") (pin "2") (pinfunction "S_2") (pintype "passive"))
      (node (ref "R2") (pin "1") (pinfunction "1_1") (pintype "passive"))
    )
    (net (code "82") (name "/RESET") (class "Default")
      (node (ref "C21") (pin "2") (pintype "passive"))
      (node (ref "C25") (pin "2") (pintype "passive"))
      (node (ref "D5") (pin "1") (pinfunction "A_1") (pintype "passive"))
      (node (ref "P7") (pin "14") (pinfunction "14_14") (pintype "passive"))
      (node (ref "R17") (pin "1") (pinfunction "1_1") (pintype "passive"))
      (node (ref "U4") (pin "30") (pinfunction "~{RESET}_30") (pintype "passive"))
    )
    (net (code "83") (name "/RXD") (class "Default")
      (node (ref "LED1") (pin "2") (pinfunction "K_2") (pintype "passive"))
      (node (ref "P6") (pin "2") (pinfunction "2_2") (pintype "passive"))
      (node (ref "R15") (pin "2") (pinfunction "2_2") (pintype "passive"))
    )
    (net (code "84") (name "/SCLK") (class "Default")
      (node (ref "P7") (pin "13") (pinfunction "13_13") (pintype "passive"))
      (node (ref "U1") (pin "16") (pinfunction "B4_16") (pintype "passive"))
      (node (ref "U4") (pin "20") (pinfunction "(PCINT1/SCK)PB1_20") (pintype "passive"))
    )
    (net (code "85") (name "/SD_CS") (class "Default")
      (node (ref "TF1") (pin "2") (pinfunction "DAT3_2") (pintype "passive"))
      (node (ref "U1") (pin "8") (pinfunction "A7_8") (pintype "passive"))
    )
    (net (code "86") (name "/SPIRAM_CS") (class "Default")
      (node (ref "U1") (pin "9") (pinfunction "A8_9") (pintype "passive"))
      (node (ref "U2") (pin "1") (pinfunction "~{CS}_1") (pintype "passive"))
    )
    (net (code "87") (name "/SS") (class "Default")
      (node (ref "U4") (pin "19") (pinfunction "(PCINT0/~{SS})PB0_19") (pintype "passive+no_connect"))
    )
    (net (code "88") (name "/TXD") (class "Default")
      (node (ref "LED2") (pin "2") (pinfunction "K_2") (pintype "passive"))
      (node (ref "P6") (pin "3") (pinfunction "3_3") (pintype "passive"))
      (node (ref "R16") (pin "2") (pinfunction "2_2") (pintype "passive"))
    )
    (net (code "89") (name "/VCC_EN") (class "Default")
      (node (ref "R3") (pin "1") (pinfunction "1_1") (pintype "passive"))
      (node (ref "R5") (pin "2") (pinfunction "2_2") (pintype "passive"))
      (node (ref "R8") (pin "1") (pinfunction "1_1") (pintype "passive"))
      (node (ref "U3") (pin "3") (pinfunction "EN_3") (pintype "passive"))
    )
    (net (code "90") (name "/XTAL1") (class "Default")
      (node (ref "C23") (pin "1") (pintype "passive"))
      (node (ref "R18") (pin "2") (pinfunction "2_2") (pintype "passive"))
      (node (ref "U4") (pin "34") (pinfunction "XTAL1_34") (pintype "passive"))
      (node (ref "Y1") (pin "2") (pinfunction "2_2") (pintype "passive"))
    )
    (net (code "91") (name "/XTAL2") (class "Default")
      (node (ref "C22") (pin "1") (pintype "passive"))
      (node (ref "R18") (pin "1") (pinfunction "1_1") (pintype "passive"))
      (node (ref "U4") (pin "33") (pinfunction "XTAL2_33") (pintype "passive"))
      (node (ref "Y1") (pin "1") (pinfunction "1_1") (pintype "passive"))
    )
    (net (code "92") (name "3.3V") (class "Default")
      (node (ref "C1") (pin "1") (pintype "passive"))
      (node (ref "C13") (pin "1") (pintype "passive"))
      (node (ref "C15") (pin "2") (pintype "passive"))
      (node (ref "C17") (pin "2") (pintype "passive"))
      (node (ref "C19") (pin "2") (pintype "passive"))
      (node (ref "C9") (pin "1") (pintype "passive"))
      (node (ref "J1") (pin "15") (pinfunction "15_15") (pintype "passive"))
      (node (ref "J1") (pin "16") (pinfunction "16_16") (pintype "passive"))
      (node (ref "L1") (pin "1") (pinfunction "1_1") (pintype "passive"))
      (node (ref "R10") (pin "1") (pinfunction "1_1") (pintype "passive"))
      (node (ref "R9") (pin "2") (pinfunction "2_2") (pintype "passive"))
      (node (ref "TF1") (pin "4") (pinfunction "VDD_4") (pintype "passive"))
      (node (ref "U1") (pin "10") (pinfunction "OE_10") (pintype "passive"))
      (node (ref "U1") (pin "2") (pinfunction "VCCA_2") (pintype "passive"))
      (node (ref "U2") (pin "8") (pinfunction "VCC_8") (pintype "passive"))
      (node (ref "U3") (pin "5") (pinfunction "VOUT_5") (pintype "passive"))
    )
    (net (code "93") (name "GND") (class "Default")
      (node (ref "C1") (pin "2") (pintype "passive"))
      (node (ref "C10") (pin "2") (pintype "passive"))
      (node (ref "C11") (pin "2") (pintype "passive"))
      (node (ref "C13") (pin "2") (pintype "passive"))
      (node (ref "C14") (pin "1") (pintype "passive"))
      (node (ref "C15") (pin "1") (pintype "passive"))
      (node (ref "C16") (pin "1") (pintype "passive"))
      (node (ref "C17") (pin "1") (pintype "passive"))
      (node (ref "C18") (pin "2") (pintype "passive"))
      (node (ref "C19") (pin "1") (pintype "passive"))
      (node (ref "C2") (pin "2") (pintype "passive"))
      (node (ref "C20") (pin "1") (pintype "passive"))
      (node (ref "C21") (pin "1") (pintype "passive"))
      (node (ref "C22") (pin "2") (pintype "passive"))
      (node (ref "C23") (pin "2") (pintype "passive"))
      (node (ref "C24") (pin "1") (pintype "passive"))
      (node (ref "C26") (pin "1") (pintype "passive"))
      (node (ref "C27") (pin "1") (pintype "passive"))
      (node (ref "C28") (pin "1") (pintype "passive"))
      (node (ref "C29") (pin "2") (pintype "passive"))
      (node (ref "C3") (pin "2") (pintype "passive"))
      (node (ref "C4") (pin "2") (pintype "passive"))
      (node (ref "C5") (pin "2") (pintype "passive"))
      (node (ref "C6") (pin "2") (pintype "passive"))
      (node (ref "C7") (pin "2") (pintype "passive"))
      (node (ref "C8") (pin "2") (pintype "passive"))
      (node (ref "C9") (pin "2") (pintype "passive"))
      (node (ref "D1") (pin "2") (pinfunction "K_2") (pintype "passive"))
      (node (ref "J1") (pin "17") (pinfunction "17_17") (pintype "passive"))
      (node (ref "J1") (pin "8") (pinfunction "8_8") (pintype "passive"))
      (node (ref "LED3") (pin "2") (pinfunction "K_2") (pintype "passive"))
      (node (ref "LED4") (pin "2") (pinfunction "K_2") (pintype "passive"))
      (node (ref "P1") (pin "2") (pinfunction "2_2") (pintype "passive"))
      (node (ref "P3") (pin "1") (pinfunction "1_1") (pintype "passive"))
      (node (ref "P4") (pin "1") (pinfunction "1_1") (pintype "passive"))
      (node (ref "P5") (pin "1") (pinfunction "1_1") (pintype "passive"))
      (node (ref "P6") (pin "5") (pinfunction "5_5") (pintype "passive"))
      (node (ref "P7") (pin "16") (pinfunction "16_16") (pintype "passive"))
      (node (ref "Q3") (pin "2") (pinfunction "E_2") (pintype "passive"))
      (node (ref "R1") (pin "2") (pinfunction "2_2") (pintype "passive"))
      (node (ref "R2") (pin "2") (pinfunction "2_2") (pintype "passive"))
      (node (ref "R5") (pin "1") (pinfunction "1_1") (pintype "passive"))
      (node (ref "R7") (pin "1") (pinfunction "1_1") (pintype "passive"))
      (node (ref "R8") (pin "2") (pinfunction "2_2") (pintype "passive"))
      (node (ref "TF1") (pin "10") (pinfunction "GND_10") (pintype "passive"))
      (node (ref "TF1") (pin "11") (pinfunction "GND_11") (pintype "passive"))
      (node (ref "TF1") (pin "12") (pinfunction "GND_12") (pintype "passive"))
      (node (ref "TF1") (pin "13") (pinfunction "GND_13") (pintype "passive"))
      (node (ref "TF1") (pin "6") (pinfunction "VSS_6") (pintype "passive"))
      (node (ref "TF1") (pin "9") (pinfunction "~{CD}_9") (pintype "passive"))
      (node (ref "U1") (pin "11") (pinfunction "GND_11") (pintype "passive"))
      (node (ref "U2") (pin "4") (pinfunction "VSS_4") (pintype "passive"))
      (node (ref "U3") (pin "2") (pinfunction "GND_2") (pintype "passive"))
      (node (ref "U4") (pin "11") (pinfunction "GND_11") (pintype "passive"))
      (node (ref "U4") (pin "32") (pinfunction "GND_32") (pintype "passive"))
      (node (ref "U4") (pin "62") (pinfunction "GND_62") (pintype "passive"))
      (node (ref "U4") (pin "81") (pinfunction "GND_81") (pintype "passive"))
      (node (ref "U4") (pin "99") (pinfunction "GND_99") (pintype "passive"))
    )
    (net (code "94") (name "Net-(C2-Pad1)") (class "Default")
      (node (ref "C2") (pin "1") (pintype "passive"))
      (node (ref "J1") (pin "18") (pinfunction "18_18") (pintype "passive"))
    )
    (net (code "95") (name "Net-(C3-Pad1)") (class "Default")
      (node (ref "C3") (pin "1") (pintype "passive"))
      (node (ref "J1") (pin "19") (pinfunction "19_19") (pintype "passive"))
    )
    (net (code "96") (name "Net-(C4-Pad1)") (class "Default")
      (node (ref "C4") (pin "1") (pintype "passive"))
      (node (ref "J1") (pin "20") (pinfunction "20_20") (pintype "passive"))
    )
    (net (code "97") (name "Net-(C6-Pad1)") (class "Default")
      (node (ref "C6") (pin "1") (pintype "passive"))
      (node (ref "J1") (pin "22") (pinfunction "22_22") (pintype "passive"))
    )
    (net (code "98") (name "Net-(C8-Pad1)") (class "Default")
      (node (ref "C8") (pin "1") (pintype "passive"))
      (node (ref "J1") (pin "24") (pinfunction "24_24") (pintype "passive"))
    )
    (net (code "99") (name "Net-(C10-Pad1)") (class "Default")
      (node (ref "C10") (pin "1") (pintype "passive"))
      (node (ref "J1") (pin "4") (pinfunction "4_4") (pintype "passive"))
    )
    (net (code "100") (name "Net-(C11-Pad1)") (class "Default")
      (node (ref "C11") (pin "1") (pintype "passive"))
      (node (ref "J1") (pin "5") (pinfunction "5_5") (pintype "passive"))
    )
    (net (code "101") (name "Net-(C25-Pad1)") (class "Default")
      (node (ref "C25") (pin "1") (pintype "passive"))
      (node (ref "P6") (pin "1") (pinfunction "1_1") (pintype "passive"))
    )
    (net (code "102") (name "Net-(D1-A)") (class "Default")
      (node (ref "C12") (pin "1") (pintype "passive"))
      (node (ref "D1") (pin "1") (pinfunction "A_1") (pintype "passive"))
      (node (ref "D2") (pin "2") (pinfunction "K_2") (pintype "passive"))
    )
    (net (code "103") (name "Net-(D3-A)") (class "Default")
      (node (ref "C12") (pin "2") (pintype "passive"))
      (node (ref "D3") (pin "1") (pinfunction "A_1") (pintype "passive"))
      (node (ref "L1") (pin "2") (pinfunction "2_2") (pintype "passive"))
      (node (ref "Q1") (pin "3") (pinfunction "D_3") (pintype "passive"))
    )
    (net (code "104") (name "Net-(LED1-A)") (class "Default")
      (node (ref "LED1") (pin "1") (pinfunction "A_1") (pintype "passive"))
      (node (ref "R11") (pin "2") (pinfunction "2_2") (pintype "passive"))
    )
    (net (code "105") (name "Net-(LED2-A)") (class "Default")
      (node (ref "LED2") (pin "1") (pinfunction "A_1") (pintype "passive"))
      (node (ref "R12") (pin "2") (pinfunction "2_2") (pintype "passive"))
    )
    (net (code "106") (name "Net-(LED3-A)") (class "Default")
      (node (ref "LED3") (pin "1") (pinfunction "A_1") (pintype "passive"))
      (node (ref "R13") (pin "2") (pinfunction "2_2") (pintype "passive"))
    )
    (net (code "107") (name "Net-(LED4-A)") (class "Default")
      (node (ref "LED4") (pin "1") (pinfunction "A_1") (pintype "passive"))
      (node (ref "R14") (pin "2") (pinfunction "2_2") (pintype "passive"))
    )
    (net (code "108") (name "Net-(Q2-G)") (class "Default")
      (node (ref "Q2") (pin "1") (pinfunction "G_1") (pintype "passive"))
      (node (ref "Q3") (pin "3") (pinfunction "C_3") (pintype "passive"))
      (node (ref "R6") (pin "2") (pinfunction "2_2") (pintype "passive"))
    )
    (net (code "109") (name "Net-(Q3-B)") (class "Default")
      (node (ref "Q3") (pin "1") (pinfunction "B_1") (pintype "passive"))
      (node (ref "R4") (pin "2") (pinfunction "2_2") (pintype "passive"))
      (node (ref "R7") (pin "2") (pinfunction "2_2") (pintype "passive"))
    )
    (net (code "110") (name "Net-(U2-~{HOLD}{slash}SIO3)") (class "Default")
      (node (ref "R10") (pin "2") (pinfunction "2_2") (pintype "passive"))
      (node (ref "U2") (pin "7") (pinfunction "~{HOLD}/SIO3_7") (pintype "passive"))
    )
    (net (code "111") (name "Net-(U3-BP)") (class "Default")
      (node (ref "C16") (pin "2") (pintype "passive"))
      (node (ref "U3") (pin "4") (pinfunction "BP_4") (pintype "passive"))
    )
    (net (code "112") (name "VCC") (class "Default")
      (node (ref "C14") (pin "2") (pintype "passive"))
      (node (ref "C18") (pin "1") (pintype "passive"))
      (node (ref "Q2") (pin "3") (pinfunction "D_3") (pintype "passive"))
      (node (ref "U1") (pin "19") (pinfunction "VCCB_19") (pintype "passive"))
      (node (ref "U3") (pin "1") (pinfunction "VIN_1") (pintype "passive"))
    )
    (net (code "113") (name "unconnected-(J1-Pad1)") (class "Default")
      (node (ref "J1") (pin "1") (pinfunction "1_1") (pintype "passive+no_connect"))
    )
    (net (code "114") (name "unconnected-(J1-Pad6)") (class "Default")
      (node (ref "J1") (pin "6") (pinfunction "6_6") (pintype "passive+no_connect"))
    )
    (net (code "115") (name "unconnected-(J1-Pad7)") (class "Default")
      (node (ref "J1") (pin "7") (pinfunction "7_7") (pintype "passive+no_connect"))
    )
    (net (code "116") (name "unconnected-(TF1-DAT1-Pad8)") (class "Default")
      (node (ref "TF1") (pin "8") (pinfunction "DAT1_8") (pintype "passive+no_connect"))
    )
    (net (code "117") (name "unconnected-(TF1-DAT2-Pad1)") (class "Default")
      (node (ref "TF1") (pin "1") (pinfunction "DAT2_1") (pintype "passive+no_connect"))
    )
    (net (code "118") (name "unconnected-(U2-SIO2-Pad3)") (class "Default")
      (node (ref "U2") (pin "3") (pinfunction "SIO2_3") (pintype "passive+no_connect"))
    )
    (net (code "119") (name "unconnected-(U4-(CLKO{slash}ICP3{slash}INT7)PE7-Pad9)") (class "Default")
      (node (ref "U4") (pin "9") (pinfunction "(CLKO/ICP3/INT7)PE7_9") (pintype "passive+no_connect"))
    )
    (net (code "120") (name "unconnected-(U4-(ICP1)PD4-Pad47)") (class "Default")
      (node (ref "U4") (pin "47") (pinfunction "(ICP1)PD4_47") (pintype "passive+no_connect"))
    )
    (net (code "121") (name "unconnected-(U4-(T1)PD6-Pad49)") (class "Default")
      (node (ref "U4") (pin "49") (pinfunction "(T1)PD6_49") (pintype "passive+no_connect"))
    )
    (net (code "122") (name "unconnected-(U4-(T3{slash}INT6)PE6-Pad8)") (class "Default")
      (node (ref "U4") (pin "8") (pinfunction "(T3/INT6)PE6_8") (pintype "passive+no_connect"))
    )
    (net (code "123") (name "unconnected-(U4-(XCK0{slash}AIN0)PE2-Pad4)") (class "Default")
      (node (ref "U4") (pin "4") (pinfunction "(XCK0/AIN0)PE2_4") (pintype "passive+no_connect"))
    )
    (net (code "124") (name "unconnected-(U4-(XCK1)PD5-Pad48)") (class "Default")
      (node (ref "U4") (pin "48") (pinfunction "(XCK1)PD5_48") (pintype "passive+no_connect"))
    )
    (net (code "125") (name "unconnected-(U4-PG3(TOSC2)-Pad28)") (class "Default")
      (node (ref "U4") (pin "28") (pinfunction "PG3(TOSC2)_28") (pintype "passive+no_connect"))
    )
    (net (code "126") (name "unconnected-(U4-PG4(TOSC1)-Pad29)") (class "Default")
      (node (ref "U4") (pin "29") (pinfunction "PG4(TOSC1)_29") (pintype "passive+no_connect"))
    )
    (net (code "127") (name "unconnected-(U4-PH2(XCK2)-Pad14)") (class "Default")
      (node (ref "U4") (pin "14") (pinfunction "PH2(XCK2)_14") (pintype "passive+no_connect"))
    )
    (net (code "128") (name "unconnected-(U4-PH7(T4)-Pad27)") (class "Default")
      (node (ref "U4") (pin "27") (pinfunction "PH7(T4)_27") (pintype "passive+no_connect"))
    )
    (net (code "129") (name "unconnected-(U4-PJ2(XCK3{slash}PCINT11)-Pad65)") (class "Default")
      (node (ref "U4") (pin "65") (pinfunction "PJ2(XCK3/PCINT11)_65") (pintype "passive+no_connect"))
    )
    (net (code "130") (name "unconnected-(U4-PJ3(PCINT12)-Pad66)") (class "Default")
      (node (ref "U4") (pin "66") (pinfunction "PJ3(PCINT12)_66") (pintype "passive+no_connect"))
    )
    (net (code "131") (name "unconnected-(U4-PJ4(PCINT13)-Pad67)") (class "Default")
      (node (ref "U4") (pin "67") (pinfunction "PJ4(PCINT13)_67") (pintype "passive+no_connect"))
    )
    (net (code "132") (name "unconnected-(U4-PJ5(PCINT14)-Pad68)") (class "Default")
      (node (ref "U4") (pin "68") (pinfunction "PJ5(PCINT14)_68") (pintype "passive+no_connect"))
    )
    (net (code "133") (name "unconnected-(U4-PJ6(PCINT15)-Pad69)") (class "Default")
      (node (ref "U4") (pin "69") (pinfunction "PJ6(PCINT15)_69") (pintype "passive+no_connect"))
    )
    (net (code "134") (name "unconnected-(U4-PJ7-Pad79)") (class "Default")
      (node (ref "U4") (pin "79") (pinfunction "PJ7_79") (pintype "passive+no_connect"))
    )
  )
)
